# JBC_PD_MCU.net
KiCad netlist of a schematic drawn in Altium Designer
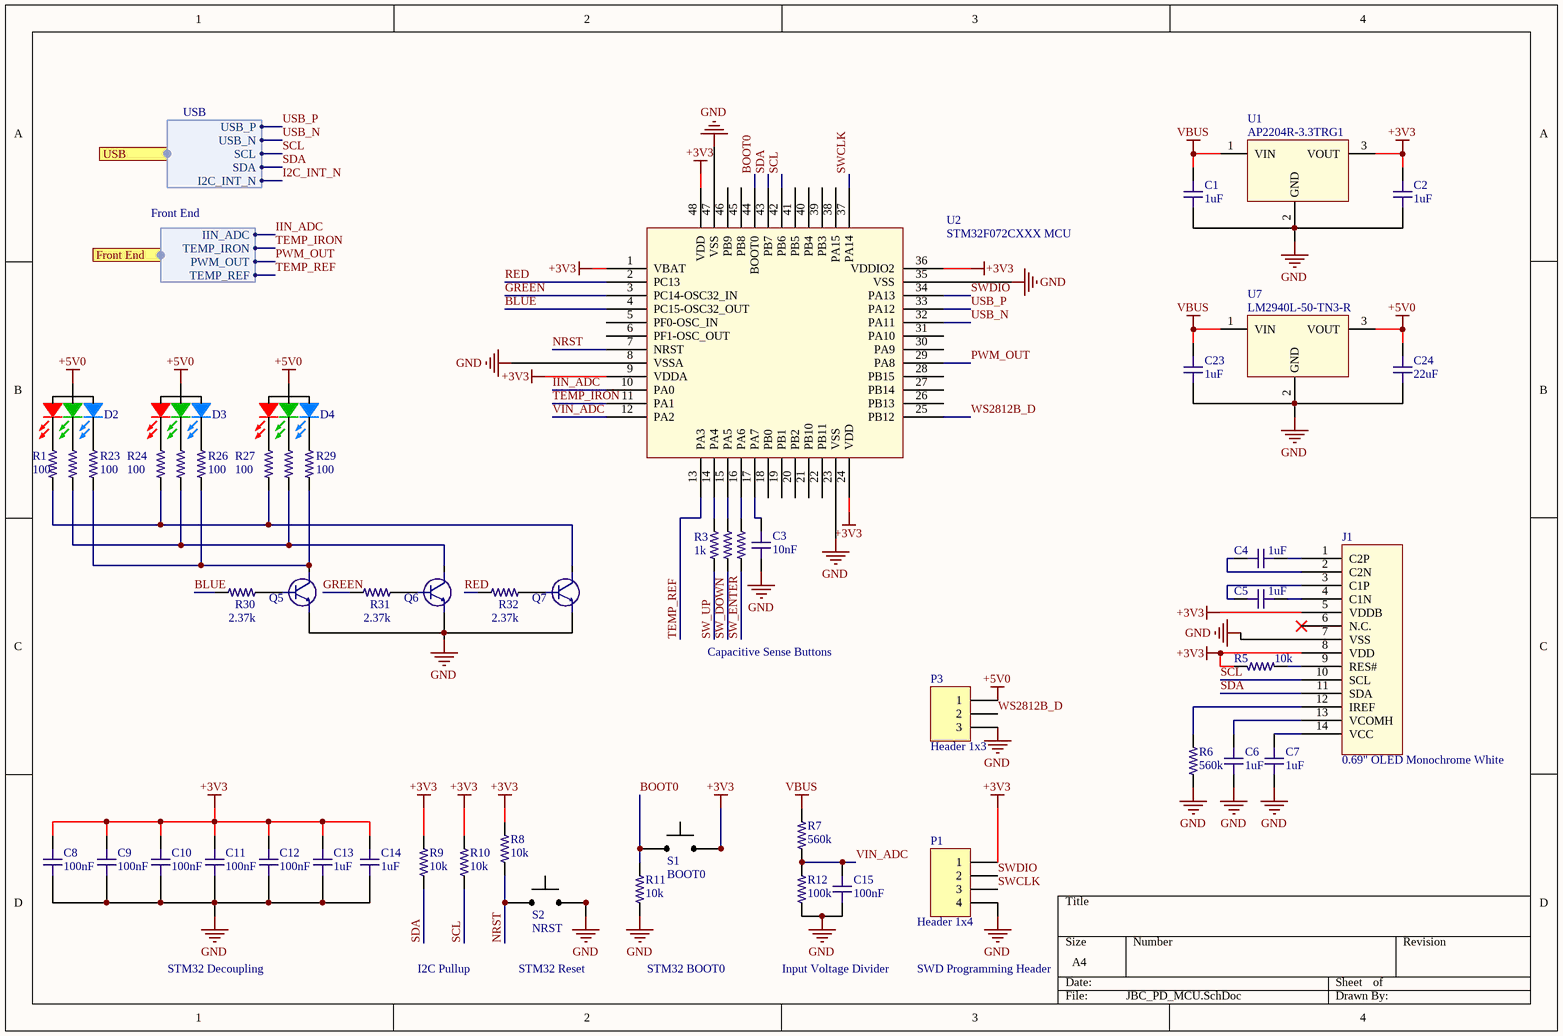
[diagram p0: JBC_PD_MCU.SchDoc]

(export (version "E")
  (design (tool "Eeschema 10.0.6"))
  (components
    (comp (ref "C1")
      (value "1uF")
      (footprint "C0603-IPC")
      (description "CAP CER 1UF 25V X7R 0603")
      (fields (field (name "Comment") "C0603 1uF 25V X7R"))
      (libsource (lib "Capacitors") (part "C0603 1uF 25V X7R"))
    )
    (comp (ref "C2")
      (value "1uF")
      (footprint "C0603-IPC")
      (description "CAP CER 1UF 25V X7R 0603")
      (fields (field (name "Comment") "C0603 1uF 25V X7R"))
      (libsource (lib "Capacitors") (part "C0603 1uF 25V X7R"))
    )
    (comp (ref "C3")
      (value "10nF")
      (footprint "C0603-IPC")
      (description "CAP CER 10000PF 50V X7R 0603")
      (fields (field (name "Comment") "Cs 10nF 50V X7R"))
      (libsource (lib "Capacitors") (part "C0603 10nF 50V X7R"))
    )
    (comp (ref "C4")
      (value "1uF")
      (footprint "C0603-IPC")
      (description "CAP CER 1UF 25V X7R 0603")
      (fields (field (name "Comment") "C0603 1uF 25V X7R"))
      (libsource (lib "Capacitors") (part "C0603 1uF 25V X7R"))
    )
    (comp (ref "C5")
      (value "1uF")
      (footprint "C0603-IPC")
      (description "CAP CER 1UF 25V X7R 0603")
      (fields (field (name "Comment") "C0603 1uF 25V X7R"))
      (libsource (lib "Capacitors") (part "C0603 1uF 25V X7R"))
    )
    (comp (ref "C6")
      (value "1uF")
      (footprint "C0603-IPC")
      (description "CAP CER 1UF 25V X7R 0603")
      (fields (field (name "Comment") "C0603 1uF 25V X7R"))
      (libsource (lib "Capacitors") (part "C0603 1uF 25V X7R"))
    )
    (comp (ref "C7")
      (value "1uF")
      (footprint "C0603-IPC")
      (description "CAP CER 1UF 25V X7R 0603")
      (fields (field (name "Comment") "C0603 1uF 25V X7R"))
      (libsource (lib "Capacitors") (part "C0603 1uF 25V X7R"))
    )
    (comp (ref "C8")
      (value "100nF")
      (footprint "C0603-IPC")
      (description "Chip Capacitor, 0603, 100nF, 25V, X7R")
      (fields (field (name "Comment") "C0603 100nF 25V X7R"))
      (libsource (lib "Capacitors") (part "C0603 100nF 25V X7R"))
    )
    (comp (ref "C9")
      (value "100nF")
      (footprint "C0603-IPC")
      (description "Chip Capacitor, 0603, 100nF, 25V, X7R")
      (fields (field (name "Comment") "C0603 100nF 25V X7R"))
      (libsource (lib "Capacitors") (part "C0603 100nF 25V X7R"))
    )
    (comp (ref "C10")
      (value "100nF")
      (footprint "C0603-IPC")
      (description "Chip Capacitor, 0603, 100nF, 25V, X7R")
      (fields (field (name "Comment") "C0603 100nF 25V X7R"))
      (libsource (lib "Capacitors") (part "C0603 100nF 25V X7R"))
    )
    (comp (ref "C11")
      (value "100nF")
      (footprint "C0603-IPC")
      (description "Chip Capacitor, 0603, 100nF, 25V, X7R")
      (fields (field (name "Comment") "C0603 100nF 25V X7R"))
      (libsource (lib "Capacitors") (part "C0603 100nF 25V X7R"))
    )
    (comp (ref "C12")
      (value "100nF")
      (footprint "C0603-IPC")
      (description "Chip Capacitor, 0603, 100nF, 25V, X7R")
      (fields (field (name "Comment") "C0603 100nF 25V X7R"))
      (libsource (lib "Capacitors") (part "C0603 100nF 25V X7R"))
    )
    (comp (ref "C13")
      (value "1uF")
      (footprint "C0603-IPC")
      (description "CAP CER 1UF 25V X7R 0603")
      (fields (field (name "Comment") "C0603 1uF 25V X7R"))
      (libsource (lib "Capacitors") (part "C0603 1uF 25V X7R"))
    )
    (comp (ref "C14")
      (value "1uF")
      (footprint "C0603-IPC")
      (description "CAP CER 1UF 25V X7R 0603")
      (fields (field (name "Comment") "C0603 1uF 25V X7R"))
      (libsource (lib "Capacitors") (part "C0603 1uF 25V X7R"))
    )
    (comp (ref "C15")
      (value "100nF")
      (footprint "C0603-IPC")
      (description "Chip Capacitor, 0603, 100nF, 25V, X7R")
      (fields (field (name "Comment") "C0603 100nF 25V X7R"))
      (libsource (lib "Capacitors") (part "C0603 100nF 25V X7R"))
    )
    (comp (ref "C23")
      (value "1uF")
      (footprint "C0603-IPC")
      (description "CAP CER 1UF 25V X7R 0603")
      (fields (field (name "Comment") "C0603 1uF 25V X7R"))
      (libsource (lib "Capacitors") (part "C0603 1uF 25V X7R"))
    )
    (comp (ref "C24")
      (value "22uF")
      (footprint "C0603-IPC")
      (description "Chip Capacitor, 0603, 22uF, 10V, X5R")
      (fields (field (name "Comment") "C0603 22uF 10V X5R"))
      (libsource (lib "Capacitors") (part "C0603 22uF 10V X5R"))
    )
    (comp (ref "D2")
      (value "RGB")
      (footprint "LED_0606_RGB_WURTH - Reverse Mount")
      (description "RGB Led 1.6 x 1.6 mm Diffused")
      (fields
        (field (name "MANUFACTURER") "Everlight")
        (field (name "MANUFACTURER PART NUMBER") "19-237/R6GHBHW-C01/2T")
      )
      (libsource (lib "Diodes") (part "Led_RGB_0606"))
    )
    (comp (ref "D3")
      (value "RGB")
      (footprint "LED_0606_RGB_WURTH - Reverse Mount")
      (description "RGB Led 1.6 x 1.6 mm Diffused")
      (fields
        (field (name "MANUFACTURER") "Everlight")
        (field (name "MANUFACTURER PART NUMBER") "19-237/R6GHBHW-C01/2T")
      )
      (libsource (lib "Diodes") (part "Led_RGB_0606"))
    )
    (comp (ref "D4")
      (value "RGB")
      (footprint "LED_0606_RGB_WURTH - Reverse Mount")
      (description "RGB Led 1.6 x 1.6 mm Diffused")
      (fields
        (field (name "MANUFACTURER") "Everlight")
        (field (name "MANUFACTURER PART NUMBER") "19-237/R6GHBHW-C01/2T")
      )
      (libsource (lib "Diodes") (part "Led_RGB_0606"))
    )
    (comp (ref "J1")
      (value "0.69\" OLED Monochrome White")
      (footprint "OLED_64x32 Bent")
      (description "0.69\" OLED Direct Solder Monochrome White")
      (fields (field (name "MANUFACTURER PART NUMBER") "UG-9616TSWCG02"))
      (libsource (lib "Connectors") (part "OLED_64x32"))
    )
    (comp (ref "P1")
      (value "Header 1x4")
      (footprint "HEADER 1X4 SMD 2.54mm")
      (description "Header, 4-Pin")
      (fields (field (name "PUBLISHER") "Altium Limited"))
      (libsource (lib "Connectors") (part "Header 1x4"))
    )
    (comp (ref "P3")
      (value "Header 1x3")
      (footprint "HEADER 1X3 SMD 2.54mm")
      (description "Header, 3-Pin")
      (fields (field (name "PUBLISHER") "Altium Limited"))
      (libsource (lib "Connectors") (part "Header 1x3"))
    )
    (comp (ref "Q5")
      (value "MMBT3904LT1G")
      (footprint "SOT23-MMBT3904")
      (description "Bipolar (BJT) Transistor NPN 40V 200mA 300MHz 300mW Surface Mount SOT-23-3 (TO-236)")
      (libsource (lib "Transistors") (part "MMBT3904LT1G"))
    )
    (comp (ref "Q6")
      (value "MMBT3904LT1G")
      (footprint "SOT23-MMBT3904")
      (description "Bipolar (BJT) Transistor NPN 40V 200mA 300MHz 300mW Surface Mount SOT-23-3 (TO-236)")
      (libsource (lib "Transistors") (part "MMBT3904LT1G"))
    )
    (comp (ref "Q7")
      (value "MMBT3904LT1G")
      (footprint "SOT23-MMBT3904")
      (description "Bipolar (BJT) Transistor NPN 40V 200mA 300MHz 300mW Surface Mount SOT-23-3 (TO-236)")
      (libsource (lib "Transistors") (part "MMBT3904LT1G"))
    )
    (comp (ref "R1")
      (value "100")
      (footprint "R0603-IPC")
      (description "RES SMD 100 OHM 1% 1/4W 0603")
      (fields (field (name "Comment") "R0603 100 1%"))
      (libsource (lib "Resistors") (part "R0603 100 1%"))
    )
    (comp (ref "R2")
      (value "R0603 1K 1%")
      (footprint "R0603-IPC")
      (description "RES SMD 1K OHM 1% 1/10W 0603")
      (fields (field (name "TOLERANCE") "±1%"))
      (libsource (lib "Resistors") (part "R0603 1K 1%"))
    )
    (comp (ref "R3")
      (value "1k")
      (footprint "R0603-IPC")
      (description "RES SMD 1K OHM 1% 1/10W 0603")
      (fields (field (name "TOLERANCE") "±1%") (field (name "Comment") "R0603 1K 1%"))
      (libsource (lib "Resistors") (part "R0603 1K 1%"))
    )
    (comp (ref "R4")
      (value "R0603 1K 1%")
      (footprint "R0603-IPC")
      (description "RES SMD 1K OHM 1% 1/10W 0603")
      (fields (field (name "TOLERANCE") "±1%"))
      (libsource (lib "Resistors") (part "R0603 1K 1%"))
    )
    (comp (ref "R5")
      (value "10k")
      (footprint "R0603-IPC")
      (description "RES SMD 10K OHM 1% 1/10W 0603")
      (fields (field (name "Comment") "R0603 10K 1%"))
      (libsource (lib "Resistors") (part "R0603 10K 1%"))
    )
    (comp (ref "R6")
      (value "560k")
      (footprint "R0603-IPC")
      (description "RES 560K OHM 1% 1/10W 0603")
      (fields (field (name "Comment") "R0603 560K 1%"))
      (libsource (lib "Resistors") (part "R0603 560K 1%"))
    )
    (comp (ref "R7")
      (value "560k")
      (footprint "R0603-IPC")
      (description "RES 560K OHM 1% 1/10W 0603")
      (fields (field (name "Comment") "R0603 560K 1%"))
      (libsource (lib "Resistors") (part "R0603 560K 1%"))
    )
    (comp (ref "R8")
      (value "10k")
      (footprint "R0603-IPC")
      (description "RES SMD 10K OHM 1% 1/10W 0603")
      (fields (field (name "Comment") "R0603 10K 1%"))
      (libsource (lib "Resistors") (part "R0603 10K 1%"))
    )
    (comp (ref "R9")
      (value "10k")
      (footprint "R0603-IPC")
      (description "RES SMD 10K OHM 1% 1/10W 0603")
      (fields (field (name "Comment") "R0603 10K 1%"))
      (libsource (lib "Resistors") (part "R0603 10K 1%"))
    )
    (comp (ref "R10")
      (value "10k")
      (footprint "R0603-IPC")
      (description "RES SMD 10K OHM 1% 1/10W 0603")
      (fields (field (name "Comment") "R0603 10K 1%"))
      (libsource (lib "Resistors") (part "R0603 10K 1%"))
    )
    (comp (ref "R11")
      (value "10k")
      (footprint "R0603-IPC")
      (description "RES SMD 10K OHM 1% 1/10W 0603")
      (fields (field (name "Comment") "R0603 10K 1%"))
      (libsource (lib "Resistors") (part "R0603 10K 1%"))
    )
    (comp (ref "R12")
      (value "100k")
      (footprint "R0603-IPC")
      (description "RES SMD 100K OHM 1% 1/10W 0603")
      (fields (field (name "Comment") "R0603 100K 1%"))
      (libsource (lib "Resistors") (part "R0603 100K 1%"))
    )
    (comp (ref "R22")
      (value "R0603 100 1%")
      (footprint "R0603-IPC")
      (description "RES SMD 100 OHM 1% 1/4W 0603")
      (libsource (lib "Resistors") (part "R0603 100 1%"))
    )
    (comp (ref "R23")
      (value "100")
      (footprint "R0603-IPC")
      (description "RES SMD 100 OHM 1% 1/4W 0603")
      (fields (field (name "Comment") "R0603 100 1%"))
      (libsource (lib "Resistors") (part "R0603 100 1%"))
    )
    (comp (ref "R24")
      (value "100")
      (footprint "R0603-IPC")
      (description "RES SMD 100 OHM 1% 1/4W 0603")
      (fields (field (name "Comment") "R0603 100 1%"))
      (libsource (lib "Resistors") (part "R0603 100 1%"))
    )
    (comp (ref "R25")
      (value "R0603 100 1%")
      (footprint "R0603-IPC")
      (description "RES SMD 100 OHM 1% 1/4W 0603")
      (libsource (lib "Resistors") (part "R0603 100 1%"))
    )
    (comp (ref "R26")
      (value "100")
      (footprint "R0603-IPC")
      (description "RES SMD 100 OHM 1% 1/4W 0603")
      (fields (field (name "Comment") "R0603 100 1%"))
      (libsource (lib "Resistors") (part "R0603 100 1%"))
    )
    (comp (ref "R27")
      (value "100")
      (footprint "R0603-IPC")
      (description "RES SMD 100 OHM 1% 1/4W 0603")
      (fields (field (name "Comment") "R0603 100 1%"))
      (libsource (lib "Resistors") (part "R0603 100 1%"))
    )
    (comp (ref "R28")
      (value "R0603 100 1%")
      (footprint "R0603-IPC")
      (description "RES SMD 100 OHM 1% 1/4W 0603")
      (libsource (lib "Resistors") (part "R0603 100 1%"))
    )
    (comp (ref "R29")
      (value "100")
      (footprint "R0603-IPC")
      (description "RES SMD 100 OHM 1% 1/4W 0603")
      (fields (field (name "Comment") "R0603 100 1%"))
      (libsource (lib "Resistors") (part "R0603 100 1%"))
    )
    (comp (ref "R30")
      (value "2.37k")
      (footprint "R0603-IPC")
      (description "RES SMD 2.37K OHM 1% 1/10W 0603")
      (fields (field (name "Comment") "R0603 2.37K 1%"))
      (libsource (lib "Resistors") (part "R0603 2.37K 1%"))
    )
    (comp (ref "R31")
      (value "2.37k")
      (footprint "R0603-IPC")
      (description "RES SMD 2.37K OHM 1% 1/10W 0603")
      (fields (field (name "Comment") "R0603 2.37K 1%"))
      (libsource (lib "Resistors") (part "R0603 2.37K 1%"))
    )
    (comp (ref "R32")
      (value "2.37k")
      (footprint "R0603-IPC")
      (description "RES SMD 2.37K OHM 1% 1/10W 0603")
      (fields (field (name "Comment") "R0603 2.37K 1%"))
      (libsource (lib "Resistors") (part "R0603 2.37K 1%"))
    )
    (comp (ref "S1")
      (value "BOOT0")
      (footprint "TL3342F260QG")
      (description "SWITCH TACTILE SPST-NO 0.05A 12V")
      (fields (field (name "MANUFACTURER PART NUMBER") "TL3342F260QG"))
      (libsource (lib "Switches") (part "SWITCH TACTILE SPST"))
    )
    (comp (ref "S2")
      (value "NRST")
      (footprint "TL3342F260QG")
      (description "SWITCH TACTILE SPST-NO 0.05A 12V")
      (fields (field (name "MANUFACTURER PART NUMBER") "TL3342F260QG"))
      (libsource (lib "Switches") (part "SWITCH TACTILE SPST"))
    )
    (comp (ref "U1")
      (value "AP2204R-3.3TRG1")
      (footprint "SOT-89")
      (description "Fixed 24V 3.3V 150mA SOT-89(SOT-89-3) Low Dropout Regulators(LDO)")
      (libsource (lib "Integrated Circuits") (part "AP2204R"))
    )
    (comp (ref "U2")
      (value "STM32F072CXXX MCU")
      (footprint "LQFP48")
      (description "32-Bit FLASH ARM® Cortex®-M0 48MHz 1.65V ~ 3.6V LQFP-48_7x7x05P ST Microelectronics RoHS")
      (libsource (lib "Integrated Circuits") (part "STM32F072CXXX"))
    )
    (comp (ref "U7")
      (value "LM2940L-50-TN3-R")
      (footprint "DPAK2")
      (description "Fixed 26V 5V 1A TO-252-2(DPAK) Low Dropout Regulators(LDO)")
      (libsource (lib "Integrated Circuits") (part "LM2940L-50-TN3-R"))
    )
  )
  (nets
    (net (code "4") (name "+3V3") (class "Default")
      (node (ref "C10") (pin "2") (pintype "passive"))
      (node (ref "C11") (pin "2") (pintype "passive"))
      (node (ref "C12") (pin "2") (pintype "passive"))
      (node (ref "C13") (pin "1") (pintype "passive"))
      (node (ref "C14") (pin "1") (pintype "passive"))
      (node (ref "C2") (pin "1") (pintype "passive"))
      (node (ref "C8") (pin "2") (pintype "passive"))
      (node (ref "C9") (pin "2") (pintype "passive"))
      (node (ref "J1") (pin "5") (pinfunction "VDDB_5") (pintype "passive"))
      (node (ref "J1") (pin "8") (pinfunction "VDD_8") (pintype "passive"))
      (node (ref "P1") (pin "1") (pinfunction "1_1") (pintype "passive"))
      (node (ref "R10") (pin "2") (pintype "passive"))
      (node (ref "R5") (pin "1") (pintype "passive"))
      (node (ref "R8") (pin "2") (pintype "passive"))
      (node (ref "R9") (pin "2") (pintype "passive"))
      (node (ref "S1") (pin "1") (pinfunction "1_1") (pintype "passive"))
      (node (ref "S1") (pin "2") (pinfunction "2_2") (pintype "passive"))
      (node (ref "U1") (pin "3") (pinfunction "VOUT_3") (pintype "passive"))
      (node (ref "U2") (pin "1") (pinfunction "VBAT_1") (pintype "passive"))
      (node (ref "U2") (pin "24") (pinfunction "VDD_24") (pintype "passive"))
      (node (ref "U2") (pin "36") (pinfunction "VDDIO2_36") (pintype "passive"))
      (node (ref "U2") (pin "48") (pinfunction "VDD_48") (pintype "passive"))
      (node (ref "U2") (pin "9") (pinfunction "VDDA_9") (pintype "passive"))
    )
    (net (code "5") (name "+5V0") (class "Default")
      (node (ref "C24") (pin "2") (pintype "passive"))
      (node (ref "D2") (pin "A") (pinfunction "A_A") (pintype "passive"))
      (node (ref "D3") (pin "A") (pinfunction "A_A") (pintype "passive"))
      (node (ref "D4") (pin "A") (pinfunction "A_A") (pintype "passive"))
      (node (ref "P3") (pin "1") (pinfunction "1_1") (pintype "passive"))
      (node (ref "U7") (pin "3") (pinfunction "VOUT_3") (pintype "passive"))
    )
    (net (code "6") (name "/BLUE") (class "Default")
      (node (ref "R30") (pin "1") (pintype "passive"))
      (node (ref "U2") (pin "4") (pinfunction "PC15-OSC32_OUT_4") (pintype "passive"))
    )
    (net (code "7") (name "/BOOT0") (class "Default")
      (node (ref "R11") (pin "2") (pintype "passive"))
      (node (ref "S1") (pin "3") (pinfunction "3_3") (pintype "passive"))
      (node (ref "S1") (pin "4") (pinfunction "4_4") (pintype "passive"))
      (node (ref "U2") (pin "44") (pinfunction "BOOT0_44") (pintype "passive"))
    )
    (net (code "8") (name "/GREEN") (class "Default")
      (node (ref "R31") (pin "1") (pintype "passive"))
      (node (ref "U2") (pin "3") (pinfunction "PC14-OSC32_IN_3") (pintype "passive"))
    )
    (net (code "10") (name "/IIN_ADC") (class "Default")
      (node (ref "U2") (pin "10") (pinfunction "PA0_10") (pintype "passive"))
    )
    (net (code "11") (name "/NRST") (class "Default")
      (node (ref "R8") (pin "1") (pintype "passive"))
      (node (ref "S2") (pin "3") (pinfunction "3_3") (pintype "passive"))
      (node (ref "S2") (pin "4") (pinfunction "4_4") (pintype "passive"))
      (node (ref "U2") (pin "7") (pinfunction "NRST_7") (pintype "passive"))
    )
    (net (code "12") (name "/PWM_OUT") (class "Default")
      (node (ref "U2") (pin "29") (pinfunction "PA8_29") (pintype "passive"))
    )
    (net (code "13") (name "/RED") (class "Default")
      (node (ref "R32") (pin "1") (pintype "passive"))
      (node (ref "U2") (pin "2") (pinfunction "PC13_2") (pintype "passive"))
    )
    (net (code "14") (name "/SCL") (class "Default")
      (node (ref "J1") (pin "10") (pinfunction "SCL_10") (pintype "passive"))
      (node (ref "R10") (pin "1") (pintype "passive"))
      (node (ref "U2") (pin "42") (pinfunction "PB6_42") (pintype "passive"))
    )
    (net (code "15") (name "/SDA") (class "Default")
      (node (ref "J1") (pin "11") (pinfunction "SDA_11") (pintype "passive"))
      (node (ref "R9") (pin "1") (pintype "passive"))
      (node (ref "U2") (pin "43") (pinfunction "PB7_43") (pintype "passive"))
    )
    (net (code "16") (name "/SWCLK") (class "Default")
      (node (ref "P1") (pin "3") (pinfunction "3_3") (pintype "passive"))
      (node (ref "U2") (pin "37") (pinfunction "PA14_37") (pintype "passive"))
    )
    (net (code "17") (name "/SWDIO") (class "Default")
      (node (ref "P1") (pin "2") (pinfunction "2_2") (pintype "passive"))
      (node (ref "U2") (pin "34") (pinfunction "PA13_34") (pintype "passive"))
    )
    (net (code "18") (name "/SW_DOWN") (class "Default") (node (ref "R2") (pin "1") (pintype "passive")))
    (net (code "19") (name "/SW_ENTER") (class "Default") (node (ref "R4") (pin "1") (pintype "passive")))
    (net (code "20") (name "/SW_UP") (class "Default") (node (ref "R3") (pin "1") (pintype "passive")))
    (net (code "21") (name "/TEMP_IRON") (class "Default")
      (node (ref "U2") (pin "11") (pinfunction "PA1_11") (pintype "passive"))
    )
    (net (code "22") (name "/TEMP_REF") (class "Default")
      (node (ref "U2") (pin "13") (pinfunction "PA3_13") (pintype "passive"))
    )
    (net (code "23") (name "/USB_N") (class "Default")
      (node (ref "U2") (pin "32") (pinfunction "PA11_32") (pintype "passive"))
    )
    (net (code "24") (name "/USB_P") (class "Default")
      (node (ref "U2") (pin "33") (pinfunction "PA12_33") (pintype "passive"))
    )
    (net (code "25") (name "/VIN_ADC") (class "Default")
      (node (ref "C15") (pin "2") (pintype "passive"))
      (node (ref "R12") (pin "2") (pintype "passive"))
      (node (ref "R7") (pin "1") (pintype "passive"))
      (node (ref "U2") (pin "12") (pinfunction "PA2_12") (pintype "passive"))
    )
    (net (code "26") (name "/WS2812B_D") (class "Default")
      (node (ref "P3") (pin "2") (pinfunction "2_2") (pintype "passive"))
      (node (ref "U2") (pin "25") (pinfunction "PB12_25") (pintype "passive"))
    )
    (net (code "29") (name "GND") (class "Default")
      (node (ref "C1") (pin "2") (pintype "passive"))
      (node (ref "C10") (pin "1") (pintype "passive"))
      (node (ref "C11") (pin "1") (pintype "passive"))
      (node (ref "C12") (pin "1") (pintype "passive"))
      (node (ref "C13") (pin "2") (pintype "passive"))
      (node (ref "C14") (pin "2") (pintype "passive"))
      (node (ref "C15") (pin "1") (pintype "passive"))
      (node (ref "C2") (pin "2") (pintype "passive"))
      (node (ref "C23") (pin "2") (pintype "passive"))
      (node (ref "C24") (pin "1") (pintype "passive"))
      (node (ref "C3") (pin "1") (pintype "passive"))
      (node (ref "C6") (pin "2") (pintype "passive"))
      (node (ref "C7") (pin "2") (pintype "passive"))
      (node (ref "C8") (pin "1") (pintype "passive"))
      (node (ref "C9") (pin "1") (pintype "passive"))
      (node (ref "J1") (pin "7") (pinfunction "VSS_7") (pintype "passive"))
      (node (ref "P1") (pin "4") (pinfunction "4_4") (pintype "passive"))
      (node (ref "P3") (pin "3") (pinfunction "3_3") (pintype "passive"))
      (node (ref "Q5") (pin "2") (pinfunction "E_2") (pintype "passive"))
      (node (ref "Q6") (pin "2") (pinfunction "E_2") (pintype "passive"))
      (node (ref "Q7") (pin "2") (pinfunction "E_2") (pintype "passive"))
      (node (ref "R11") (pin "1") (pintype "passive"))
      (node (ref "R12") (pin "1") (pintype "passive"))
      (node (ref "R6") (pin "1") (pintype "passive"))
      (node (ref "S2") (pin "1") (pinfunction "1_1") (pintype "passive"))
      (node (ref "S2") (pin "2") (pinfunction "2_2") (pintype "passive"))
      (node (ref "U1") (pin "2") (pinfunction "GND_2") (pintype "passive"))
      (node (ref "U2") (pin "23") (pinfunction "VSS_23") (pintype "passive"))
      (node (ref "U2") (pin "35") (pinfunction "VSS_35") (pintype "passive"))
      (node (ref "U2") (pin "47") (pinfunction "VSS_47") (pintype "passive"))
      (node (ref "U2") (pin "8") (pinfunction "VSSA_8") (pintype "passive"))
      (node (ref "U7") (pin "2") (pinfunction "GND_2") (pintype "passive"))
    )
    (net (code "30") (name "Net-(D2-PadBK)") (class "Default")
      (node (ref "D2") (pin "BK") (pinfunction "BK_BK") (pintype "passive"))
      (node (ref "R23") (pin "2") (pintype "passive"))
    )
    (net (code "31") (name "Net-(D2-PadGK)") (class "Default")
      (node (ref "D2") (pin "GK") (pinfunction "GK_GK") (pintype "passive"))
      (node (ref "R22") (pin "2") (pintype "passive"))
    )
    (net (code "32") (name "Net-(D2-PadRK)") (class "Default")
      (node (ref "D2") (pin "RK") (pinfunction "RK_RK") (pintype "passive"))
      (node (ref "R1") (pin "2") (pintype "passive"))
    )
    (net (code "33") (name "Net-(D3-PadBK)") (class "Default")
      (node (ref "D3") (pin "BK") (pinfunction "BK_BK") (pintype "passive"))
      (node (ref "R26") (pin "2") (pintype "passive"))
    )
    (net (code "34") (name "Net-(D3-PadGK)") (class "Default")
      (node (ref "D3") (pin "GK") (pinfunction "GK_GK") (pintype "passive"))
      (node (ref "R25") (pin "2") (pintype "passive"))
    )
    (net (code "35") (name "Net-(D3-PadRK)") (class "Default")
      (node (ref "D3") (pin "RK") (pinfunction "RK_RK") (pintype "passive"))
      (node (ref "R24") (pin "2") (pintype "passive"))
    )
    (net (code "36") (name "Net-(D4-PadBK)") (class "Default")
      (node (ref "D4") (pin "BK") (pinfunction "BK_BK") (pintype "passive"))
      (node (ref "R29") (pin "2") (pintype "passive"))
    )
    (net (code "37") (name "Net-(D4-PadGK)") (class "Default")
      (node (ref "D4") (pin "GK") (pinfunction "GK_GK") (pintype "passive"))
      (node (ref "R28") (pin "2") (pintype "passive"))
    )
    (net (code "38") (name "Net-(D4-PadRK)") (class "Default")
      (node (ref "D4") (pin "RK") (pinfunction "RK_RK") (pintype "passive"))
      (node (ref "R27") (pin "2") (pintype "passive"))
    )
    (net (code "39") (name "Net-(J1-C1N)") (class "Default")
      (node (ref "C5") (pin "2") (pintype "passive"))
      (node (ref "J1") (pin "4") (pinfunction "C1N_4") (pintype "passive"))
    )
    (net (code "40") (name "Net-(J1-C1P)") (class "Default")
      (node (ref "C5") (pin "1") (pintype "passive"))
      (node (ref "J1") (pin "3") (pinfunction "C1P_3") (pintype "passive"))
    )
    (net (code "41") (name "Net-(J1-C2N)") (class "Default")
      (node (ref "C4") (pin "1") (pintype "passive"))
      (node (ref "J1") (pin "2") (pinfunction "C2N_2") (pintype "passive"))
    )
    (net (code "42") (name "Net-(J1-C2P)") (class "Default")
      (node (ref "C4") (pin "2") (pintype "passive"))
      (node (ref "J1") (pin "1") (pinfunction "C2P_1") (pintype "passive"))
    )
    (net (code "43") (name "Net-(J1-IREF)") (class "Default")
      (node (ref "J1") (pin "12") (pinfunction "IREF_12") (pintype "passive"))
      (node (ref "R6") (pin "2") (pintype "passive"))
    )
    (net (code "44") (name "Net-(J1-RES#)") (class "Default")
      (node (ref "J1") (pin "9") (pinfunction "RES#_9") (pintype "passive"))
      (node (ref "R5") (pin "2") (pintype "passive"))
    )
    (net (code "45") (name "Net-(J1-VCC)") (class "Default")
      (node (ref "C7") (pin "1") (pintype "passive"))
      (node (ref "J1") (pin "14") (pinfunction "VCC_14") (pintype "passive"))
    )
    (net (code "46") (name "Net-(J1-VCOMH)") (class "Default")
      (node (ref "C6") (pin "1") (pintype "passive"))
      (node (ref "J1") (pin "13") (pinfunction "VCOMH_13") (pintype "passive"))
    )
    (net (code "47") (name "Net-(Q5-B)") (class "Default")
      (node (ref "Q5") (pin "1") (pinfunction "B_1") (pintype "passive"))
      (node (ref "R30") (pin "2") (pintype "passive"))
    )
    (net (code "48") (name "Net-(Q5-C)") (class "Default")
      (node (ref "Q5") (pin "3") (pinfunction "C_3") (pintype "passive"))
      (node (ref "R23") (pin "1") (pintype "passive"))
      (node (ref "R26") (pin "1") (pintype "passive"))
      (node (ref "R29") (pin "1") (pintype "passive"))
    )
    (net (code "49") (name "Net-(Q6-B)") (class "Default")
      (node (ref "Q6") (pin "1") (pinfunction "B_1") (pintype "passive"))
      (node (ref "R31") (pin "2") (pintype "passive"))
    )
    (net (code "50") (name "Net-(Q6-C)") (class "Default")
      (node (ref "Q6") (pin "3") (pinfunction "C_3") (pintype "passive"))
      (node (ref "R22") (pin "1") (pintype "passive"))
      (node (ref "R25") (pin "1") (pintype "passive"))
      (node (ref "R28") (pin "1") (pintype "passive"))
    )
    (net (code "51") (name "Net-(Q7-B)") (class "Default")
      (node (ref "Q7") (pin "1") (pinfunction "B_1") (pintype "passive"))
      (node (ref "R32") (pin "2") (pintype "passive"))
    )
    (net (code "52") (name "Net-(Q7-C)") (class "Default")
      (node (ref "Q7") (pin "3") (pinfunction "C_3") (pintype "passive"))
      (node (ref "R1") (pin "1") (pintype "passive"))
      (node (ref "R24") (pin "1") (pintype "passive"))
      (node (ref "R27") (pin "1") (pintype "passive"))
    )
    (net (code "53") (name "Net-(U2-PA4)") (class "Default")
      (node (ref "R3") (pin "2") (pintype "passive"))
      (node (ref "U2") (pin "14") (pinfunction "PA4_14") (pintype "passive"))
    )
    (net (code "54") (name "Net-(U2-PA5)") (class "Default")
      (node (ref "R2") (pin "2") (pintype "passive"))
      (node (ref "U2") (pin "15") (pinfunction "PA5_15") (pintype "passive"))
    )
    (net (code "55") (name "Net-(U2-PA6)") (class "Default")
      (node (ref "R4") (pin "2") (pintype "passive"))
      (node (ref "U2") (pin "16") (pinfunction "PA6_16") (pintype "passive"))
    )
    (net (code "56") (name "Net-(U2-PA7)") (class "Default")
      (node (ref "C3") (pin "2") (pintype "passive"))
      (node (ref "U2") (pin "17") (pinfunction "PA7_17") (pintype "passive"))
    )
    (net (code "57") (name "VBUS") (class "Default")
      (node (ref "C1") (pin "1") (pintype "passive"))
      (node (ref "C23") (pin "1") (pintype "passive"))
      (node (ref "R7") (pin "2") (pintype "passive"))
      (node (ref "U1") (pin "1") (pinfunction "VIN_1") (pintype "passive"))
      (node (ref "U7") (pin "1") (pinfunction "VIN_1") (pintype "passive"))
    )
    (net (code "58") (name "unconnected-(J1-N.C.-Pad6)") (class "Default")
      (node (ref "J1") (pin "6") (pinfunction "N.C._6") (pintype "passive+no_connect"))
    )
    (net (code "59") (name "unconnected-(U2-PA9-Pad30)") (class "Default")
      (node (ref "U2") (pin "30") (pinfunction "PA9_30") (pintype "passive"))
    )
    (net (code "60") (name "unconnected-(U2-PA10-Pad31)") (class "Default")
      (node (ref "U2") (pin "31") (pinfunction "PA10_31") (pintype "passive"))
    )
    (net (code "61") (name "unconnected-(U2-PA15-Pad38)") (class "Default")
      (node (ref "U2") (pin "38") (pinfunction "PA15_38") (pintype "passive"))
    )
    (net (code "62") (name "unconnected-(U2-PB0-Pad18)") (class "Default")
      (node (ref "U2") (pin "18") (pinfunction "PB0_18") (pintype "passive"))
    )
    (net (code "63") (name "unconnected-(U2-PB1-Pad19)") (class "Default")
      (node (ref "U2") (pin "19") (pinfunction "PB1_19") (pintype "passive"))
    )
    (net (code "64") (name "unconnected-(U2-PB2-Pad20)") (class "Default")
      (node (ref "U2") (pin "20") (pinfunction "PB2_20") (pintype "passive"))
    )
    (net (code "65") (name "unconnected-(U2-PB3-Pad39)") (class "Default")
      (node (ref "U2") (pin "39") (pinfunction "PB3_39") (pintype "passive"))
    )
    (net (code "66") (name "unconnected-(U2-PB4-Pad40)") (class "Default")
      (node (ref "U2") (pin "40") (pinfunction "PB4_40") (pintype "passive"))
    )
    (net (code "67") (name "unconnected-(U2-PB5-Pad41)") (class "Default")
      (node (ref "U2") (pin "41") (pinfunction "PB5_41") (pintype "passive"))
    )
    (net (code "68") (name "unconnected-(U2-PB8-Pad45)") (class "Default")
      (node (ref "U2") (pin "45") (pinfunction "PB8_45") (pintype "passive"))
    )
    (net (code "69") (name "unconnected-(U2-PB9-Pad46)") (class "Default")
      (node (ref "U2") (pin "46") (pinfunction "PB9_46") (pintype "passive"))
    )
    (net (code "70") (name "unconnected-(U2-PB10-Pad21)") (class "Default")
      (node (ref "U2") (pin "21") (pinfunction "PB10_21") (pintype "passive"))
    )
    (net (code "71") (name "unconnected-(U2-PB11-Pad22)") (class "Default")
      (node (ref "U2") (pin "22") (pinfunction "PB11_22") (pintype "passive"))
    )
    (net (code "72") (name "unconnected-(U2-PB13-Pad26)") (class "Default")
      (node (ref "U2") (pin "26") (pinfunction "PB13_26") (pintype "passive"))
    )
    (net (code "73") (name "unconnected-(U2-PB14-Pad27)") (class "Default")
      (node (ref "U2") (pin "27") (pinfunction "PB14_27") (pintype "passive"))
    )
    (net (code "74") (name "unconnected-(U2-PB15-Pad28)") (class "Default")
      (node (ref "U2") (pin "28") (pinfunction "PB15_28") (pintype "passive"))
    )
    (net (code "75") (name "unconnected-(U2-PF0-OSC_IN-Pad5)") (class "Default")
      (node (ref "U2") (pin "5") (pinfunction "PF0-OSC_IN_5") (pintype "passive"))
    )
    (net (code "76") (name "unconnected-(U2-PF1-OSC_OUT-Pad6)") (class "Default")
      (node (ref "U2") (pin "6") (pinfunction "PF1-OSC_OUT_6") (pintype "passive"))
    )
  )
)
